# PAM2401_Module.net
KiCad netlist of a schematic drawn in EAGLE
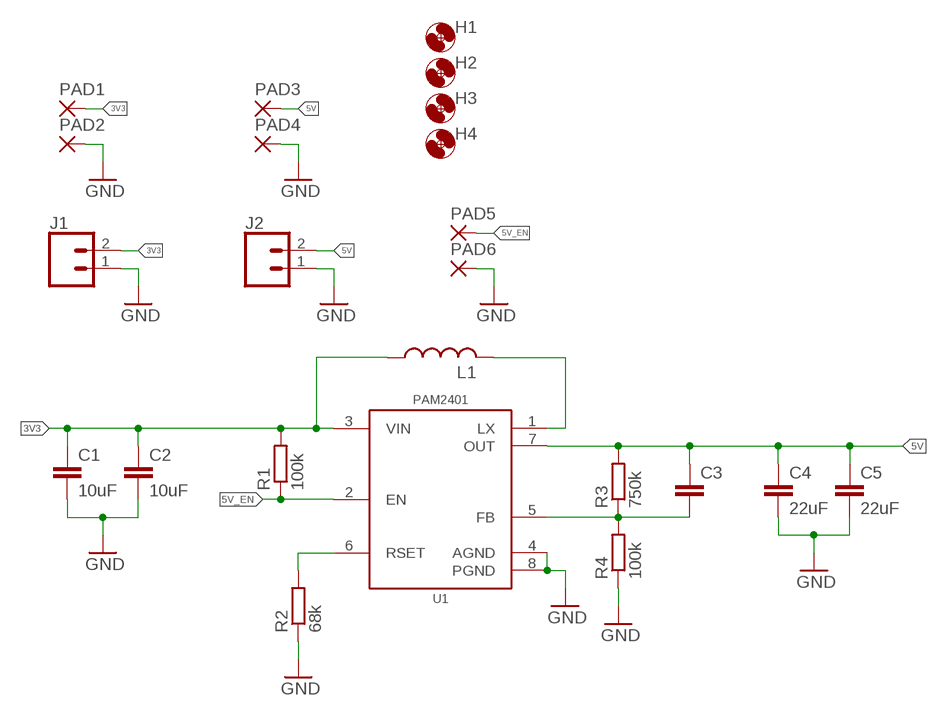
[diagram p0: schematic, sheet 1]

(export (version "E")
  (design (tool "Eeschema 10.0.6"))
  (components
    (comp (ref "C1")
      (value "10uF")
      (footprint "eagle-import:C0805")
      (fields (field (name "MF") "Murata") (field (name "MPN") "GRM21BR61C106KE15K"))
      (libsource (lib "eagle-import") (part "C-EUC080510UF"))
    )
    (comp (ref "C2")
      (value "10uF")
      (footprint "eagle-import:C0805")
      (fields (field (name "MF") "Murata") (field (name "MPN") "GRM21BR61C106KE15K"))
      (libsource (lib "eagle-import") (part "C-EUC080510UF"))
    )
    (comp (ref "C3")
      (value "C-EUC0603")
      (footprint "eagle-import:C0603")
      (libsource (lib "eagle-import") (part "C-EUC0603"))
    )
    (comp (ref "C4")
      (value "22uF")
      (footprint "eagle-import:C0805")
      (fields (field (name "MF") "Murata") (field (name "MPN") "GRM219R61C226ME15L"))
      (libsource (lib "eagle-import") (part "C-EUC080522UF"))
    )
    (comp (ref "C5")
      (value "22uF")
      (footprint "eagle-import:C0805")
      (fields (field (name "MF") "Murata") (field (name "MPN") "GRM219R61C226ME15L"))
      (libsource (lib "eagle-import") (part "C-EUC080522UF"))
    )
    (comp (ref "H1")
      (value "MOUNTING_HOLE2_NP")
      (footprint "eagle-import:2_56")
      (fields (field (name "MPN") "DNP"))
      (libsource (lib "eagle-import") (part "MOUNTING_HOLE2_NP"))
    )
    (comp (ref "H2")
      (value "MOUNTING_HOLE2_NP")
      (footprint "eagle-import:2_56")
      (fields (field (name "MPN") "DNP"))
      (libsource (lib "eagle-import") (part "MOUNTING_HOLE2_NP"))
    )
    (comp (ref "H3")
      (value "MOUNTING_HOLE2_NP")
      (footprint "eagle-import:2_56")
      (fields (field (name "MPN") "DNP"))
      (libsource (lib "eagle-import") (part "MOUNTING_HOLE2_NP"))
    )
    (comp (ref "H4")
      (value "MOUNTING_HOLE2_NP")
      (footprint "eagle-import:2_56")
      (fields (field (name "MPN") "DNP"))
      (libsource (lib "eagle-import") (part "MOUNTING_HOLE2_NP"))
    )
    (comp (ref "J1")
      (value "CONN_023.5MM_ROUND_RESTRICT")
      (footprint "eagle-import:SCREWTERMINAL-3.5MM-2_ROUND_RESTRICT")
      (fields (field (name "MF") "On Shore") (field (name "MPN") "OSTTE020161"))
      (libsource (lib "eagle-import") (part "CONN_023.5MM_ROUND_RESTRICT"))
    )
    (comp (ref "J2")
      (value "CONN_023.5MM_ROUND_RESTRICT")
      (footprint "eagle-import:SCREWTERMINAL-3.5MM-2_ROUND_RESTRICT")
      (fields (field (name "MF") "On Shore") (field (name "MPN") "OSTTE020161"))
      (libsource (lib "eagle-import") (part "CONN_023.5MM_ROUND_RESTRICT"))
    )
    (comp (ref "L1")
      (value "INDUCTOR_MAPI_2.5X2")
      (footprint "eagle-import:WE-MAPI(2.5X2)")
      (libsource (lib "eagle-import") (part "INDUCTOR_MAPI_2.5X2"))
    )
    (comp (ref "PAD1")
      (value "SMD5")
      (footprint "eagle-import:SMD2,54-5,08")
      (libsource (lib "eagle-import") (part "SMD5"))
    )
    (comp (ref "PAD2")
      (value "SMD5")
      (footprint "eagle-import:SMD2,54-5,08")
      (libsource (lib "eagle-import") (part "SMD5"))
    )
    (comp (ref "PAD3")
      (value "SMD5")
      (footprint "eagle-import:SMD2,54-5,08")
      (libsource (lib "eagle-import") (part "SMD5"))
    )
    (comp (ref "PAD4")
      (value "SMD5")
      (footprint "eagle-import:SMD2,54-5,08")
      (libsource (lib "eagle-import") (part "SMD5"))
    )
    (comp (ref "PAD5")
      (value "SMD2")
      (footprint "eagle-import:SMD1,27-2,54")
      (fields (field (name "MPN") "DNP"))
      (libsource (lib "eagle-import") (part "SMD2"))
    )
    (comp (ref "PAD6")
      (value "SMD2")
      (footprint "eagle-import:SMD1,27-2,54")
      (fields (field (name "MPN") "DNP"))
      (libsource (lib "eagle-import") (part "SMD2"))
    )
    (comp (ref "R1")
      (value "100k")
      (footprint "eagle-import:R0603")
      (fields (field (name "MF") "Yageo") (field (name "MPN") "RC0603FR-07100KL"))
      (libsource (lib "eagle-import") (part "R-EU_R0603100K"))
    )
    (comp (ref "R2")
      (value "68k")
      (footprint "eagle-import:R0603")
      (fields (field (name "MF") "Yageo"))
      (libsource (lib "eagle-import") (part "R-EU_R0603"))
    )
    (comp (ref "R3")
      (value "750k")
      (footprint "eagle-import:R0603")
      (fields (field (name "MF") "Yageo") (field (name "MPN") "RC0603FR-07750KL"))
      (libsource (lib "eagle-import") (part "R-EU_R0603750K"))
    )
    (comp (ref "R4")
      (value "100k")
      (footprint "eagle-import:R0603")
      (fields (field (name "MF") "Yageo") (field (name "MPN") "RC0603FR-07100KL"))
      (libsource (lib "eagle-import") (part "R-EU_R0603100K"))
    )
    (comp (ref "U1")
      (value "PAM2401MSOP")
      (footprint "eagle-import:MSOP_8")
      (fields (field (name "MF") "Diodes Inc") (field (name "MPN") "PAM2401SCADJ"))
      (libsource (lib "eagle-import") (part "PAM2401MSOP"))
    )
  )
  (nets
    (net (code "1") (name "3V3") (class "Default")
      (node (ref "C1") (pin "1") (pinfunction "1_1") (pintype "passive"))
      (node (ref "C2") (pin "1") (pinfunction "1_1") (pintype "passive"))
      (node (ref "J1") (pin "2") (pinfunction "2_2") (pintype "passive"))
      (node (ref "L1") (pin "P$1") (pinfunction "1_P$1") (pintype "passive"))
      (node (ref "PAD1") (pin "1") (pinfunction "P_1") (pintype "passive"))
      (node (ref "R1") (pin "2") (pinfunction "2_2") (pintype "passive"))
      (node (ref "U1") (pin "3") (pinfunction "VIN_3") (pintype "power_in"))
    )
    (net (code "2") (name "5V") (class "Default")
      (node (ref "C3") (pin "1") (pinfunction "1_1") (pintype "passive"))
      (node (ref "C4") (pin "1") (pinfunction "1_1") (pintype "passive"))
      (node (ref "C5") (pin "1") (pinfunction "1_1") (pintype "passive"))
      (node (ref "J2") (pin "2") (pinfunction "2_2") (pintype "passive"))
      (node (ref "PAD3") (pin "1") (pinfunction "P_1") (pintype "passive"))
      (node (ref "R3") (pin "2") (pinfunction "2_2") (pintype "passive"))
      (node (ref "U1") (pin "7") (pinfunction "OUT_7") (pintype "power_in"))
    )
    (net (code "3") (name "5V_EN") (class "Default")
      (node (ref "PAD5") (pin "1") (pinfunction "P_1") (pintype "passive"))
      (node (ref "R1") (pin "1") (pinfunction "1_1") (pintype "passive"))
      (node (ref "U1") (pin "2") (pinfunction "EN_2") (pintype "input"))
    )
    (net (code "4") (name "GND") (class "Default")
      (node (ref "C1") (pin "2") (pinfunction "2_2") (pintype "passive"))
      (node (ref "C2") (pin "2") (pinfunction "2_2") (pintype "passive"))
      (node (ref "C4") (pin "2") (pinfunction "2_2") (pintype "passive"))
      (node (ref "C5") (pin "2") (pinfunction "2_2") (pintype "passive"))
      (node (ref "J1") (pin "1") (pinfunction "1_1") (pintype "passive"))
      (node (ref "J2") (pin "1") (pinfunction "1_1") (pintype "passive"))
      (node (ref "PAD2") (pin "1") (pinfunction "P_1") (pintype "passive"))
      (node (ref "PAD4") (pin "1") (pinfunction "P_1") (pintype "passive"))
      (node (ref "PAD6") (pin "1") (pinfunction "P_1") (pintype "passive"))
      (node (ref "R2") (pin "1") (pinfunction "1_1") (pintype "passive"))
      (node (ref "R4") (pin "1") (pinfunction "1_1") (pintype "passive"))
      (node (ref "U1") (pin "4") (pinfunction "AGND_4") (pintype "power_in"))
      (node (ref "U1") (pin "8") (pinfunction "PGND_8") (pintype "power_in"))
    )
    (net (code "5") (name "Net-(L1-2)") (class "Default")
      (node (ref "L1") (pin "P$2") (pinfunction "2_P$2") (pintype "passive"))
      (node (ref "U1") (pin "1") (pinfunction "LX_1") (pintype "power_in"))
    )
    (net (code "6") (name "Net-(U1-FB)") (class "Default")
      (node (ref "C3") (pin "2") (pinfunction "2_2") (pintype "passive"))
      (node (ref "R3") (pin "1") (pinfunction "1_1") (pintype "passive"))
      (node (ref "R4") (pin "2") (pinfunction "2_2") (pintype "passive"))
      (node (ref "U1") (pin "5") (pinfunction "FB_5") (pintype "input"))
    )
    (net (code "7") (name "Net-(U1-RSET)") (class "Default")
      (node (ref "R2") (pin "2") (pinfunction "2_2") (pintype "passive"))
      (node (ref "U1") (pin "6") (pinfunction "RSET_6") (pintype "input"))
    )
  )
)
